# EA3501.net
KiCad netlist of a schematic drawn in Altium Designer
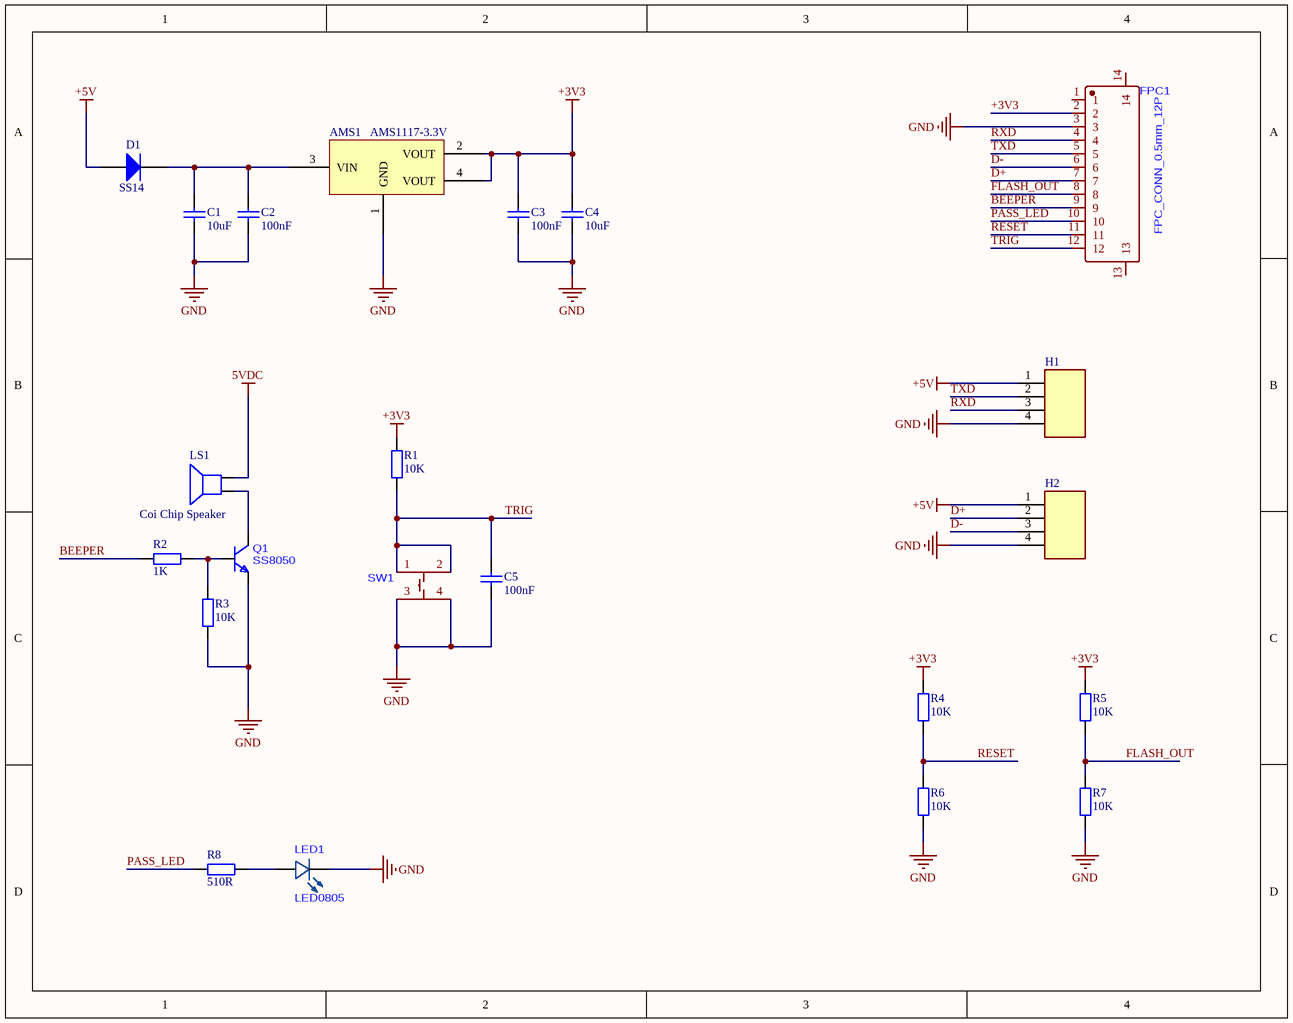
[diagram p0: EA3501.SchDoc]

(export (version "E")
  (design (tool "Eeschema 10.0.6"))
  (components
    (comp (ref "AMS1")
      (value "AMS1117-3.3V")
      (footprint "SOT223")
      (description "Dán")
      (libsource (lib "IC") (part "AMS1117 SMD"))
    )
    (comp (ref "C1")
      (value "10uF")
      (footprint "Cap0603")
      (description "Capacitor SMD 0603")
      (libsource (lib "General") (part "Cap 0603"))
    )
    (comp (ref "C2")
      (value "100nF")
      (footprint "Cap0603")
      (description "Capacitor SMD 0603")
      (libsource (lib "General") (part "Cap 0603"))
    )
    (comp (ref "C3")
      (value "100nF")
      (footprint "Cap0603")
      (description "Capacitor SMD 0603")
      (libsource (lib "General") (part "Cap 0603"))
    )
    (comp (ref "C4")
      (value "10uF")
      (footprint "Cap0603")
      (description "Capacitor SMD 0603")
      (libsource (lib "General") (part "Cap 0603"))
    )
    (comp (ref "C5")
      (value "100nF")
      (footprint "Cap0603")
      (description "Capacitor SMD 0603")
      (libsource (lib "General") (part "Cap 0603"))
    )
    (comp (ref "D1") (value "SS14") (footprint "SMA(DO-214AC)") (libsource (lib "General") (part "DIODE")))
    (comp (ref "FPC1")
      (value "FPC_CONN_0.5mm_12P")
      (footprint "FPC-SMD_12P-P0.50_FPC-05F-12PH20")
      (libsource (lib "Connector") (part "FPC_CONN_0.5mm_12P"))
    )
    (comp (ref "H1")
      (value "CONN_HDR_4P_1.25")
      (footprint "CONN_HDR_4P_1.25mm")
      (libsource (lib "Connector") (part "CONN_HDR_4P_1.25"))
    )
    (comp (ref "H2")
      (value "CONN_HDR_4P_1.25")
      (footprint "CONN_HDR_4P_1.25mm")
      (libsource (lib "Connector") (part "CONN_HDR_4P_1.25"))
    )
    (comp (ref "LED1")
      (value "LED0805")
      (footprint "LED0805-GR")
      (libsource (lib "General") (part "LED0805"))
    )
    (comp (ref "LS1")
      (value "Coi Chip Speaker")
      (footprint "Coi Chip Speacker")
      (description "Còi chip")
      (libsource (lib "Component") (part "Coi Chip Speaker"))
    )
    (comp (ref "Q1") (value "SS8050") (footprint "SOT-23") (libsource (lib "TranFet") (part "SS8050")))
    (comp (ref "R1")
      (value "10K")
      (footprint "R0603")
      (description "RES SMD 0603")
      (fields
        (field (name "MANUFACTURER") "Vishay Dale")
        (field (name "MANUFACTURER PART NUMBER") "CRCW040210K0FKED")
      )
      (libsource (lib "General") (part "RES 0603"))
    )
    (comp (ref "R2")
      (value "1K")
      (footprint "R0603")
      (description "RES SMD 0603")
      (fields
        (field (name "MANUFACTURER") "Vishay Dale")
        (field (name "MANUFACTURER PART NUMBER") "CRCW040210K0FKED")
      )
      (libsource (lib "General") (part "RES 0603"))
    )
    (comp (ref "R3")
      (value "10K")
      (footprint "R0603")
      (description "RES SMD 0603")
      (fields
        (field (name "MANUFACTURER") "Vishay Dale")
        (field (name "MANUFACTURER PART NUMBER") "CRCW040210K0FKED")
      )
      (libsource (lib "General") (part "RES 0603"))
    )
    (comp (ref "R4")
      (value "10K")
      (footprint "R0603")
      (description "RES SMD 0603")
      (fields
        (field (name "MANUFACTURER") "Vishay Dale")
        (field (name "MANUFACTURER PART NUMBER") "CRCW040210K0FKED")
      )
      (libsource (lib "General") (part "RES 0603"))
    )
    (comp (ref "R5")
      (value "10K")
      (footprint "R0603")
      (description "RES SMD 0603")
      (fields
        (field (name "MANUFACTURER") "Vishay Dale")
        (field (name "MANUFACTURER PART NUMBER") "CRCW040210K0FKED")
      )
      (libsource (lib "General") (part "RES 0603"))
    )
    (comp (ref "R6")
      (value "10K")
      (footprint "R0603")
      (description "RES SMD 0603")
      (fields
        (field (name "MANUFACTURER") "Vishay Dale")
        (field (name "MANUFACTURER PART NUMBER") "CRCW040210K0FKED")
      )
      (libsource (lib "General") (part "RES 0603"))
    )
    (comp (ref "R7")
      (value "10K")
      (footprint "R0603")
      (description "RES SMD 0603")
      (fields
        (field (name "MANUFACTURER") "Vishay Dale")
        (field (name "MANUFACTURER PART NUMBER") "CRCW040210K0FKED")
      )
      (libsource (lib "General") (part "RES 0603"))
    )
    (comp (ref "R8")
      (value "510R")
      (footprint "R0603")
      (description "RES SMD 0603")
      (fields
        (field (name "MANUFACTURER") "Vishay Dale")
        (field (name "MANUFACTURER PART NUMBER") "CRCW040210K0FKED")
      )
      (libsource (lib "General") (part "RES 0603"))
    )
    (comp (ref "SW1")
      (value "SW_4P_")
      (footprint "SW-SMD_4P-L5.1-W5.1-P3.70-LS6.4_YZA-044-1.5")
      (libsource (lib "General") (part "SW_4P_"))
    )
  )
  (nets
    (net (code "1") (name "+3V3") (class "Default")
      (node (ref "AMS1") (pin "2") (pinfunction "VOUT_2") (pintype "passive"))
      (node (ref "AMS1") (pin "4") (pinfunction "VOUT_4") (pintype "passive"))
      (node (ref "C3") (pin "1") (pinfunction "1_1") (pintype "passive"))
      (node (ref "C4") (pin "1") (pinfunction "1_1") (pintype "passive"))
      (node (ref "FPC1") (pin "2") (pinfunction "2_2") (pintype "passive"))
      (node (ref "R1") (pin "2") (pinfunction "2_2") (pintype "passive"))
      (node (ref "R4") (pin "2") (pinfunction "2_2") (pintype "passive"))
      (node (ref "R5") (pin "2") (pinfunction "2_2") (pintype "passive"))
    )
    (net (code "2") (name "+5V") (class "Default")
      (node (ref "D1") (pin "1") (pinfunction "A_1") (pintype "passive"))
      (node (ref "H1") (pin "1") (pinfunction "1_1") (pintype "passive"))
      (node (ref "H2") (pin "1") (pinfunction "1_1") (pintype "passive"))
    )
    (net (code "3") (name "/BEEPER") (class "Default")
      (node (ref "FPC1") (pin "9") (pinfunction "9_9") (pintype "passive"))
      (node (ref "R2") (pin "1") (pinfunction "1_1") (pintype "passive"))
    )
    (net (code "4") (name "/D+") (class "Default")
      (node (ref "FPC1") (pin "7") (pinfunction "7_7") (pintype "passive"))
      (node (ref "H2") (pin "2") (pinfunction "2_2") (pintype "passive"))
    )
    (net (code "5") (name "/D-") (class "Default")
      (node (ref "FPC1") (pin "6") (pinfunction "6_6") (pintype "passive"))
      (node (ref "H2") (pin "3") (pinfunction "3_3") (pintype "passive"))
    )
    (net (code "6") (name "/FLASH_OUT") (class "Default")
      (node (ref "FPC1") (pin "8") (pinfunction "8_8") (pintype "passive"))
      (node (ref "R5") (pin "1") (pinfunction "1_1") (pintype "passive"))
      (node (ref "R7") (pin "1") (pinfunction "1_1") (pintype "passive"))
    )
    (net (code "7") (name "/PASS_LED") (class "Default")
      (node (ref "FPC1") (pin "10") (pinfunction "10_10") (pintype "passive"))
      (node (ref "R8") (pin "1") (pinfunction "1_1") (pintype "passive"))
    )
    (net (code "8") (name "/RESET") (class "Default")
      (node (ref "FPC1") (pin "11") (pinfunction "11_11") (pintype "passive"))
      (node (ref "R4") (pin "1") (pinfunction "1_1") (pintype "passive"))
      (node (ref "R6") (pin "1") (pinfunction "1_1") (pintype "passive"))
    )
    (net (code "9") (name "/RXD") (class "Default")
      (node (ref "FPC1") (pin "4") (pinfunction "4_4") (pintype "passive"))
      (node (ref "H1") (pin "3") (pinfunction "3_3") (pintype "passive"))
    )
    (net (code "10") (name "/TRIG") (class "Default")
      (node (ref "C5") (pin "1") (pinfunction "1_1") (pintype "passive"))
      (node (ref "FPC1") (pin "12") (pinfunction "12_12") (pintype "passive"))
      (node (ref "R1") (pin "1") (pinfunction "1_1") (pintype "passive"))
      (node (ref "SW1") (pin "1") (pinfunction "A_1") (pintype "passive"))
      (node (ref "SW1") (pin "2") (pinfunction "B_2") (pintype "passive"))
    )
    (net (code "11") (name "/TXD") (class "Default")
      (node (ref "FPC1") (pin "5") (pinfunction "5_5") (pintype "passive"))
      (node (ref "H1") (pin "2") (pinfunction "2_2") (pintype "passive"))
    )
    (net (code "12") (name "5VDC") (class "Default")
      (node (ref "LS1") (pin "2") (pinfunction "2_2") (pintype "passive"))
    )
    (net (code "13") (name "GND") (class "Default")
      (node (ref "AMS1") (pin "1") (pinfunction "GND_1") (pintype "passive"))
      (node (ref "C1") (pin "2") (pinfunction "2_2") (pintype "passive"))
      (node (ref "C2") (pin "2") (pinfunction "2_2") (pintype "passive"))
      (node (ref "C3") (pin "2") (pinfunction "2_2") (pintype "passive"))
      (node (ref "C4") (pin "2") (pinfunction "2_2") (pintype "passive"))
      (node (ref "C5") (pin "2") (pinfunction "2_2") (pintype "passive"))
      (node (ref "FPC1") (pin "3") (pinfunction "3_3") (pintype "passive"))
      (node (ref "H1") (pin "4") (pinfunction "4_4") (pintype "passive"))
      (node (ref "H2") (pin "4") (pinfunction "4_4") (pintype "passive"))
      (node (ref "LED1") (pin "1") (pinfunction "-_1") (pintype "passive"))
      (node (ref "Q1") (pin "2") (pinfunction "E_2") (pintype "passive"))
      (node (ref "R3") (pin "1") (pinfunction "1_1") (pintype "passive"))
      (node (ref "R6") (pin "2") (pinfunction "2_2") (pintype "passive"))
      (node (ref "R7") (pin "2") (pinfunction "2_2") (pintype "passive"))
      (node (ref "SW1") (pin "3") (pinfunction "C_3") (pintype "passive"))
      (node (ref "SW1") (pin "4") (pinfunction "D_4") (pintype "passive"))
    )
    (net (code "14") (name "Net-(AMS1-VIN)") (class "Default")
      (node (ref "AMS1") (pin "3") (pinfunction "VIN_3") (pintype "passive"))
      (node (ref "C1") (pin "1") (pinfunction "1_1") (pintype "passive"))
      (node (ref "C2") (pin "1") (pinfunction "1_1") (pintype "passive"))
      (node (ref "D1") (pin "2") (pinfunction "K_2") (pintype "passive"))
    )
    (net (code "15") (name "Net-(LED1-+)") (class "Default")
      (node (ref "LED1") (pin "2") (pinfunction "+_2") (pintype "passive"))
      (node (ref "R8") (pin "2") (pinfunction "2_2") (pintype "passive"))
    )
    (net (code "16") (name "Net-(Q1-B)") (class "Default")
      (node (ref "Q1") (pin "1") (pinfunction "B_1") (pintype "passive"))
      (node (ref "R2") (pin "2") (pinfunction "2_2") (pintype "passive"))
      (node (ref "R3") (pin "2") (pinfunction "2_2") (pintype "passive"))
    )
    (net (code "17") (name "Net-(Q1-C)") (class "Default")
      (node (ref "LS1") (pin "1") (pinfunction "1_1") (pintype "passive"))
      (node (ref "Q1") (pin "3") (pinfunction "C_3") (pintype "passive"))
    )
    (net (code "18") (name "unconnected-(FPC1-Pad1)") (class "Default")
      (node (ref "FPC1") (pin "1") (pinfunction "1_1") (pintype "passive"))
    )
    (net (code "19") (name "unconnected-(FPC1-Pad13)") (class "Default")
      (node (ref "FPC1") (pin "13") (pinfunction "13_13") (pintype "passive"))
    )
    (net (code "20") (name "unconnected-(FPC1-Pad14)") (class "Default")
      (node (ref "FPC1") (pin "14") (pinfunction "14_14") (pintype "passive"))
    )
  )
)
